# untitled.net
KiCad netlist of a schematic drawn in EAGLE
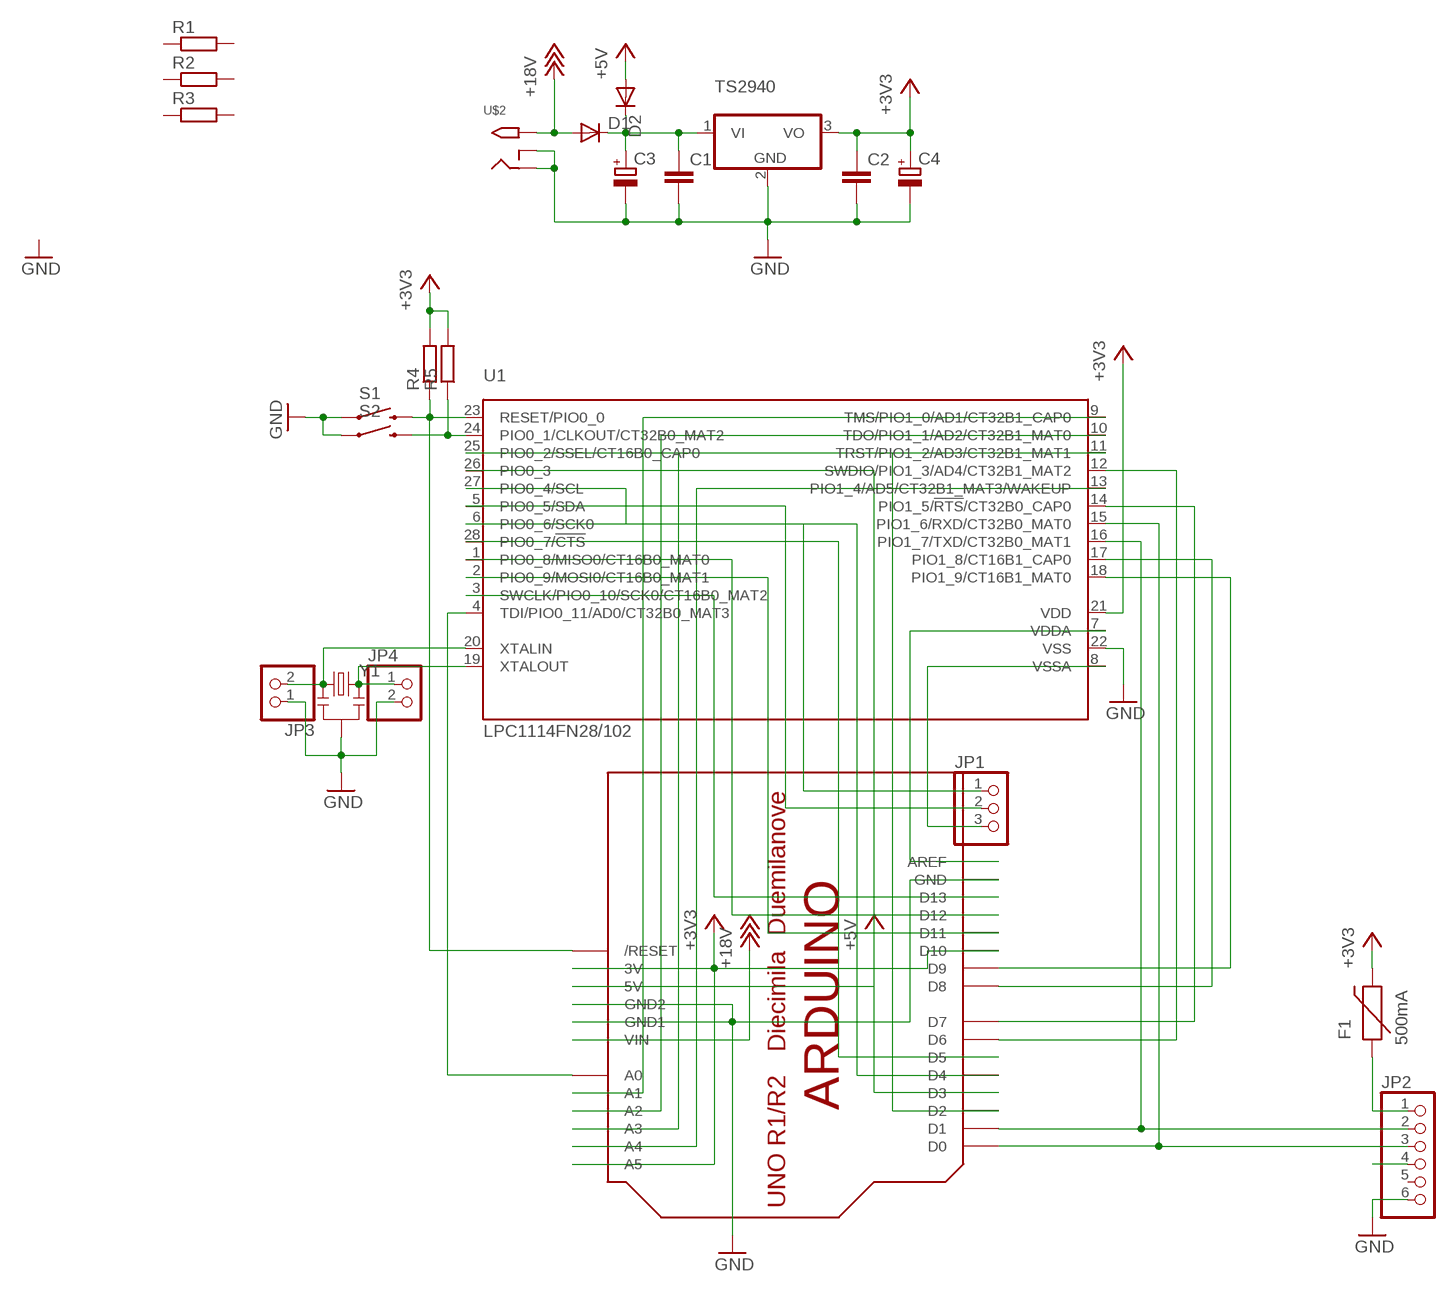
[diagram p0: schematic, sheet 1]

(export (version "E")
  (design (tool "Eeschema 10.0.6"))
  (components
    (comp (ref "C1")
      (value "C-EU025-025X050")
      (footprint "eagle-import:C025-025X050")
      (libsource (lib "eagle-import") (part "C-EU025-025X050"))
    )
    (comp (ref "C2")
      (value "C-EU025-025X050")
      (footprint "eagle-import:C025-025X050")
      (libsource (lib "eagle-import") (part "C-EU025-025X050"))
    )
    (comp (ref "C3")
      (value "CPOL-EUE2.5-6")
      (footprint "eagle-import:E2,5-6")
      (libsource (lib "eagle-import") (part "CPOL-EUE2.5-6"))
    )
    (comp (ref "C4")
      (value "CPOL-EUE2.5-6")
      (footprint "eagle-import:E2,5-6")
      (libsource (lib "eagle-import") (part "CPOL-EUE2.5-6"))
    )
    (comp (ref "D1")
      (value "DIODE-C1702-05")
      (footprint "eagle-import:C1702-05")
      (libsource (lib "eagle-import") (part "DIODE-C1702-05"))
    )
    (comp (ref "D2")
      (value "DIODE-C1702-05")
      (footprint "eagle-import:C1702-05")
      (libsource (lib "eagle-import") (part "DIODE-C1702-05"))
    )
    (comp (ref "F1")
      (value "500mA")
      (footprint "eagle-import:PTC")
      (libsource (lib "eagle-import") (part "PTCPTH"))
    )
    (comp (ref "JP1")
      (value "PINHD-1X3")
      (footprint "eagle-import:1X03")
      (libsource (lib "eagle-import") (part "PINHD-1X3"))
    )
    (comp (ref "JP2")
      (value "PINHD-1X6/90")
      (footprint "eagle-import:1X06_90")
      (libsource (lib "eagle-import") (part "PINHD-1X6/90"))
    )
    (comp (ref "JP3")
      (value "PINHD-1X2")
      (footprint "eagle-import:1X02")
      (libsource (lib "eagle-import") (part "PINHD-1X2"))
    )
    (comp (ref "JP4")
      (value "PINHD-1X2")
      (footprint "eagle-import:1X02")
      (libsource (lib "eagle-import") (part "PINHD-1X2"))
    )
    (comp (ref "R1")
      (value "R-EU_0204/7")
      (footprint "eagle-import:0204_7")
      (libsource (lib "eagle-import") (part "R-EU_0204/7"))
    )
    (comp (ref "R2")
      (value "R-EU_0204/7")
      (footprint "eagle-import:0204_7")
      (libsource (lib "eagle-import") (part "R-EU_0204/7"))
    )
    (comp (ref "R3")
      (value "R-EU_0204/7")
      (footprint "eagle-import:0204_7")
      (libsource (lib "eagle-import") (part "R-EU_0204/7"))
    )
    (comp (ref "R4")
      (value "R-EU_0204/7")
      (footprint "eagle-import:0204_7")
      (libsource (lib "eagle-import") (part "R-EU_0204/7"))
    )
    (comp (ref "R5")
      (value "R-EU_0204/7")
      (footprint "eagle-import:0204_7")
      (libsource (lib "eagle-import") (part "R-EU_0204/7"))
    )
    (comp (ref "S1")
      (value "SWITCH-MOMENTARY-2PTH")
      (footprint "eagle-import:TACTILE-PTH")
      (libsource (lib "eagle-import") (part "SWITCH-MOMENTARY-2PTH"))
    )
    (comp (ref "S2")
      (value "SWITCH-MOMENTARY-2PTH")
      (footprint "eagle-import:TACTILE-PTH")
      (libsource (lib "eagle-import") (part "SWITCH-MOMENTARY-2PTH"))
    )
    (comp (ref "TS2940")
      (value "7805T")
      (footprint "eagle-import:TO220H")
      (libsource (lib "eagle-import") (part "78T05"))
    )
    (comp (ref "U$1")
      (value "ARDUINO-BPLACE")
      (footprint "eagle-import:ARDUINO-BPLACE")
      (libsource (lib "eagle-import") (part "ARDUINO-BPLACE"))
    )
    (comp (ref "U$2")
      (value "2.1MMJACKTHM")
      (footprint "eagle-import:PJ-102A")
      (libsource (lib "eagle-import") (part "2.1MMJACKTHM"))
    )
    (comp (ref "U1")
      (value "LPC1114FN28/102")
      (footprint "eagle-import:SOT117")
      (libsource (lib "eagle-import") (part "LPC1114FN28/102"))
    )
    (comp (ref "Y1")
      (value "RESONATORPTH")
      (footprint "eagle-import:RESONATOR-PTH")
      (libsource (lib "eagle-import") (part "RESONATORPTH"))
    )
  )
  (nets
    (net (code "1") (name "+3V3") (class "Default")
      (node (ref "C2") (pin "1") (pinfunction "1_1") (pintype "passive"))
      (node (ref "C4") (pin "+") (pinfunction "+_+") (pintype "passive"))
      (node (ref "F1") (pin "P$2") (pinfunction "2_P$2") (pintype "bidirectional"))
      (node (ref "R4") (pin "2") (pinfunction "2_2") (pintype "passive"))
      (node (ref "R5") (pin "2") (pinfunction "2_2") (pintype "passive"))
      (node (ref "TS2940") (pin "3") (pinfunction "VO_3") (pintype "passive"))
      (node (ref "U$1") (pin "3V") (pinfunction "3V_3V") (pintype "power_in"))
      (node (ref "U$1") (pin "A5") (pinfunction "A5_A5") (pintype "bidirectional"))
      (node (ref "U$1") (pin "D10") (pinfunction "D10_D10") (pintype "bidirectional"))
      (node (ref "U1") (pin "21") (pinfunction "VDD_21") (pintype "power_in"))
    )
    (net (code "2") (name "+5V") (class "Default")
      (node (ref "D2") (pin "A") (pinfunction "A_A") (pintype "passive"))
      (node (ref "U$1") (pin "5V") (pinfunction "5V_5V") (pintype "power_in"))
    )
    (net (code "3") (name "+18V") (class "Default")
      (node (ref "D1") (pin "A") (pinfunction "A_A") (pintype "passive"))
      (node (ref "U$1") (pin "VIN") (pinfunction "VIN_VIN") (pintype "power_in"))
      (node (ref "U$2") (pin "TIP") (pinfunction "TIP_TIP") (pintype "bidirectional"))
    )
    (net (code "4") (name "GND") (class "Default")
      (node (ref "C1") (pin "2") (pinfunction "2_2") (pintype "passive"))
      (node (ref "C2") (pin "2") (pinfunction "2_2") (pintype "passive"))
      (node (ref "C3") (pin "-") (pinfunction "-_-") (pintype "passive"))
      (node (ref "C4") (pin "-") (pinfunction "-_-") (pintype "passive"))
      (node (ref "JP2") (pin "6") (pinfunction "6_6") (pintype "passive"))
      (node (ref "JP3") (pin "1") (pinfunction "1_1") (pintype "passive"))
      (node (ref "JP4") (pin "2") (pinfunction "2_2") (pintype "passive"))
      (node (ref "S1") (pin "1") (pinfunction "1_1") (pintype "passive"))
      (node (ref "S2") (pin "1") (pinfunction "1_1") (pintype "passive"))
      (node (ref "TS2940") (pin "2") (pinfunction "GND_2") (pintype "passive"))
      (node (ref "U$1") (pin "GND") (pinfunction "GND_GND") (pintype "power_in"))
      (node (ref "U$1") (pin "GND1") (pinfunction "GND1_GND1") (pintype "power_in"))
      (node (ref "U$1") (pin "GND2") (pinfunction "GND2_GND2") (pintype "power_in"))
      (node (ref "U$2") (pin "RING") (pinfunction "RING_RING") (pintype "bidirectional"))
      (node (ref "U$2") (pin "RING_SW") (pinfunction "RING_SW_RING_SW") (pintype "bidirectional"))
      (node (ref "U1") (pin "22") (pinfunction "VSS_22") (pintype "power_in"))
      (node (ref "Y1") (pin "2") (pinfunction "2_2") (pintype "passive"))
    )
    (net (code "5") (name "Net-(F1-1)") (class "Default")
      (node (ref "F1") (pin "P$1") (pinfunction "1_P$1") (pintype "bidirectional"))
      (node (ref "JP2") (pin "1") (pinfunction "1_1") (pintype "passive"))
    )
    (net (code "6") (name "Net-(S1-2)") (class "Default")
      (node (ref "R4") (pin "1") (pinfunction "1_1") (pintype "passive"))
      (node (ref "S1") (pin "3") (pinfunction "2_3") (pintype "passive"))
      (node (ref "U$1") (pin "RESET") (pinfunction "/RESET_RESET") (pintype "bidirectional"))
      (node (ref "U1") (pin "23") (pinfunction "RESET/PIO0_0_23") (pintype "bidirectional"))
    )
    (net (code "7") (name "Net-(S2-2)") (class "Default")
      (node (ref "R5") (pin "1") (pinfunction "1_1") (pintype "passive"))
      (node (ref "S2") (pin "3") (pinfunction "2_3") (pintype "passive"))
      (node (ref "U1") (pin "24") (pinfunction "PIO0_1/CLKOUT/CT32B0_MAT2_24") (pintype "bidirectional"))
    )
    (net (code "8") (name "Net-(TS2940-VI)") (class "Default")
      (node (ref "C1") (pin "1") (pinfunction "1_1") (pintype "passive"))
      (node (ref "C3") (pin "+") (pinfunction "+_+") (pintype "passive"))
      (node (ref "D1") (pin "C") (pinfunction "C_C") (pintype "passive"))
      (node (ref "D2") (pin "C") (pinfunction "C_C") (pintype "passive"))
      (node (ref "TS2940") (pin "1") (pinfunction "VI_1") (pintype "input"))
    )
    (net (code "9") (name "Net-(U1-PIO0_2{slash}SSEL{slash}CT16B0_CAP0)") (class "Default")
      (node (ref "U$1") (pin "D2") (pinfunction "D2_D2") (pintype "bidirectional"))
      (node (ref "U1") (pin "25") (pinfunction "PIO0_2/SSEL/CT16B0_CAP0_25") (pintype "bidirectional"))
    )
    (net (code "10") (name "Net-(U1-PIO0_3)") (class "Default")
      (node (ref "U$1") (pin "D3") (pinfunction "D3_D3") (pintype "bidirectional"))
      (node (ref "U1") (pin "26") (pinfunction "PIO0_3_26") (pintype "bidirectional"))
    )
    (net (code "11") (name "Net-(U1-PIO0_4{slash}SCL)") (class "Default")
      (node (ref "JP1") (pin "1") (pinfunction "1_1") (pintype "passive"))
      (node (ref "U1") (pin "27") (pinfunction "PIO0_4/SCL_27") (pintype "bidirectional"))
    )
    (net (code "12") (name "Net-(U1-PIO0_5{slash}SDA)") (class "Default")
      (node (ref "JP1") (pin "2") (pinfunction "2_2") (pintype "passive"))
      (node (ref "U1") (pin "5") (pinfunction "PIO0_5/SDA_5") (pintype "bidirectional"))
    )
    (net (code "13") (name "Net-(U1-PIO0_6{slash}SCK0)") (class "Default")
      (node (ref "U$1") (pin "D4") (pinfunction "D4_D4") (pintype "bidirectional"))
      (node (ref "U1") (pin "6") (pinfunction "PIO0_6/SCK0_6") (pintype "bidirectional"))
    )
    (net (code "14") (name "Net-(U1-PIO0_7{slash}~{CTS})") (class "Default")
      (node (ref "U$1") (pin "D5") (pinfunction "D5_D5") (pintype "bidirectional"))
      (node (ref "U1") (pin "28") (pinfunction "PIO0_7/~{CTS}_28") (pintype "bidirectional"))
    )
    (net (code "15") (name "Net-(U1-PIO0_8{slash}MISO0{slash}CT16B0_MAT0)") (class "Default")
      (node (ref "U$1") (pin "D12") (pinfunction "D12_D12") (pintype "bidirectional"))
      (node (ref "U1") (pin "1") (pinfunction "PIO0_8/MISO0/CT16B0_MAT0_1") (pintype "bidirectional"))
    )
    (net (code "16") (name "Net-(U1-PIO0_9{slash}MOSI0{slash}CT16B0_MAT1)") (class "Default")
      (node (ref "U$1") (pin "D11") (pinfunction "D11_D11") (pintype "bidirectional"))
      (node (ref "U1") (pin "2") (pinfunction "PIO0_9/MOSI0/CT16B0_MAT1_2") (pintype "bidirectional"))
    )
    (net (code "17") (name "Net-(U1-PIO1_4{slash}AD5{slash}CT32B1_MAT3{slash}WAKEUP)") (class "Default")
      (node (ref "U$1") (pin "A4") (pinfunction "A4_A4") (pintype "bidirectional"))
      (node (ref "U1") (pin "13") (pinfunction "PIO1_4/AD5/CT32B1_MAT3/WAKEUP_13") (pintype "bidirectional"))
    )
    (net (code "18") (name "Net-(U1-PIO1_5{slash}~{RTS}{slash}CT32B0_CAP0)") (class "Default")
      (node (ref "U$1") (pin "D7") (pinfunction "D7_D7") (pintype "bidirectional"))
      (node (ref "U1") (pin "14") (pinfunction "PIO1_5/~{RTS}/CT32B0_CAP0_14") (pintype "bidirectional"))
    )
    (net (code "19") (name "Net-(U1-PIO1_6{slash}RXD{slash}CT32B0_MAT0)") (class "Default")
      (node (ref "JP2") (pin "3") (pinfunction "3_3") (pintype "passive"))
      (node (ref "U$1") (pin "D0") (pinfunction "D0_D0") (pintype "bidirectional"))
      (node (ref "U1") (pin "15") (pinfunction "PIO1_6/RXD/CT32B0_MAT0_15") (pintype "bidirectional"))
    )
    (net (code "20") (name "Net-(U1-PIO1_7{slash}TXD{slash}CT32B0_MAT1)") (class "Default")
      (node (ref "JP2") (pin "2") (pinfunction "2_2") (pintype "passive"))
      (node (ref "U$1") (pin "D1") (pinfunction "D1_D1") (pintype "bidirectional"))
      (node (ref "U1") (pin "16") (pinfunction "PIO1_7/TXD/CT32B0_MAT1_16") (pintype "bidirectional"))
    )
    (net (code "21") (name "Net-(U1-PIO1_8{slash}CT16B1_CAP0)") (class "Default")
      (node (ref "U$1") (pin "D8") (pinfunction "D8_D8") (pintype "bidirectional"))
      (node (ref "U1") (pin "17") (pinfunction "PIO1_8/CT16B1_CAP0_17") (pintype "bidirectional"))
    )
    (net (code "22") (name "Net-(U1-PIO1_9{slash}CT16B1_MAT0)") (class "Default")
      (node (ref "U$1") (pin "D9") (pinfunction "D9_D9") (pintype "bidirectional"))
      (node (ref "U1") (pin "18") (pinfunction "PIO1_9/CT16B1_MAT0_18") (pintype "bidirectional"))
    )
    (net (code "23") (name "Net-(U1-SWCLK{slash}PIO0_10{slash}SCK0{slash}CT16B0_MAT2)") (class "Default")
      (node (ref "U$1") (pin "D13") (pinfunction "D13_D13") (pintype "bidirectional"))
      (node (ref "U1") (pin "3") (pinfunction "SWCLK/PIO0_10/SCK0/CT16B0_MAT2_3") (pintype "bidirectional"))
    )
    (net (code "24") (name "Net-(U1-SWDIO{slash}PIO1_3{slash}AD4{slash}CT32B1_MAT2)") (class "Default")
      (node (ref "U$1") (pin "D6") (pinfunction "D6_D6") (pintype "bidirectional"))
      (node (ref "U1") (pin "12") (pinfunction "SWDIO/PIO1_3/AD4/CT32B1_MAT2_12") (pintype "bidirectional"))
    )
    (net (code "25") (name "Net-(U1-TDI{slash}PIO0_11{slash}AD0{slash}CT32B0_MAT3)") (class "Default")
      (node (ref "U$1") (pin "A0") (pinfunction "A0_A0") (pintype "bidirectional"))
      (node (ref "U1") (pin "4") (pinfunction "TDI/PIO0_11/AD0/CT32B0_MAT3_4") (pintype "bidirectional"))
    )
    (net (code "26") (name "Net-(U1-TDO{slash}PIO1_1{slash}AD2{slash}CT32B1_MAT0)") (class "Default")
      (node (ref "U$1") (pin "A2") (pinfunction "A2_A2") (pintype "bidirectional"))
      (node (ref "U1") (pin "10") (pinfunction "TDO/PIO1_1/AD2/CT32B1_MAT0_10") (pintype "bidirectional"))
    )
    (net (code "27") (name "Net-(U1-TMS{slash}PIO1_0{slash}AD1{slash}CT32B1_CAP0)") (class "Default")
      (node (ref "U$1") (pin "A1") (pinfunction "A1_A1") (pintype "bidirectional"))
      (node (ref "U1") (pin "9") (pinfunction "TMS/PIO1_0/AD1/CT32B1_CAP0_9") (pintype "bidirectional"))
    )
    (net (code "28") (name "Net-(U1-TRST{slash}PIO1_2{slash}AD3{slash}CT32B1_MAT1)") (class "Default")
      (node (ref "U$1") (pin "A3") (pinfunction "A3_A3") (pintype "bidirectional"))
      (node (ref "U1") (pin "11") (pinfunction "TRST/PIO1_2/AD3/CT32B1_MAT1_11") (pintype "bidirectional"))
    )
    (net (code "29") (name "Net-(U1-VDDA)") (class "Default")
      (node (ref "U$1") (pin "AREF") (pinfunction "AREF_AREF") (pintype "bidirectional"))
      (node (ref "U1") (pin "7") (pinfunction "VDDA_7") (pintype "power_in"))
    )
    (net (code "30") (name "Net-(U1-VSSA)") (class "Default")
      (node (ref "JP1") (pin "3") (pinfunction "3_3") (pintype "passive"))
      (node (ref "U1") (pin "8") (pinfunction "VSSA_8") (pintype "power_in"))
    )
    (net (code "31") (name "Net-(U1-XTALIN)") (class "Default")
      (node (ref "JP3") (pin "2") (pinfunction "2_2") (pintype "passive"))
      (node (ref "U1") (pin "20") (pinfunction "XTALIN_20") (pintype "input"))
      (node (ref "Y1") (pin "1") (pinfunction "1_1") (pintype "passive"))
    )
    (net (code "32") (name "Net-(U1-XTALOUT)") (class "Default")
      (node (ref "JP4") (pin "1") (pinfunction "1_1") (pintype "passive"))
      (node (ref "U1") (pin "19") (pinfunction "XTALOUT_19") (pintype "output"))
      (node (ref "Y1") (pin "3") (pinfunction "3_3") (pintype "passive"))
    )
    (net (code "33") (name "unconnected-(JP2-Pad4)") (class "Default")
      (node (ref "JP2") (pin "4") (pinfunction "4_4") (pintype "passive"))
    )
    (net (code "34") (name "unconnected-(JP2-Pad5)") (class "Default")
      (node (ref "JP2") (pin "5") (pinfunction "5_5") (pintype "passive"))
    )
    (net (code "35") (name "unconnected-(R1-Pad1)") (class "Default")
      (node (ref "R1") (pin "1") (pinfunction "1_1") (pintype "passive"))
    )
    (net (code "36") (name "unconnected-(R1-Pad2)") (class "Default")
      (node (ref "R1") (pin "2") (pinfunction "2_2") (pintype "passive"))
    )
    (net (code "37") (name "unconnected-(R2-Pad1)") (class "Default")
      (node (ref "R2") (pin "1") (pinfunction "1_1") (pintype "passive"))
    )
    (net (code "38") (name "unconnected-(R2-Pad2)") (class "Default")
      (node (ref "R2") (pin "2") (pinfunction "2_2") (pintype "passive"))
    )
    (net (code "39") (name "unconnected-(R3-Pad1)") (class "Default")
      (node (ref "R3") (pin "1") (pinfunction "1_1") (pintype "passive"))
    )
    (net (code "40") (name "unconnected-(R3-Pad2)") (class "Default")
      (node (ref "R3") (pin "2") (pinfunction "2_2") (pintype "passive"))
    )
  )
)
